# PowerBoard.net
KiCad netlist of a schematic drawn in Altium Designer
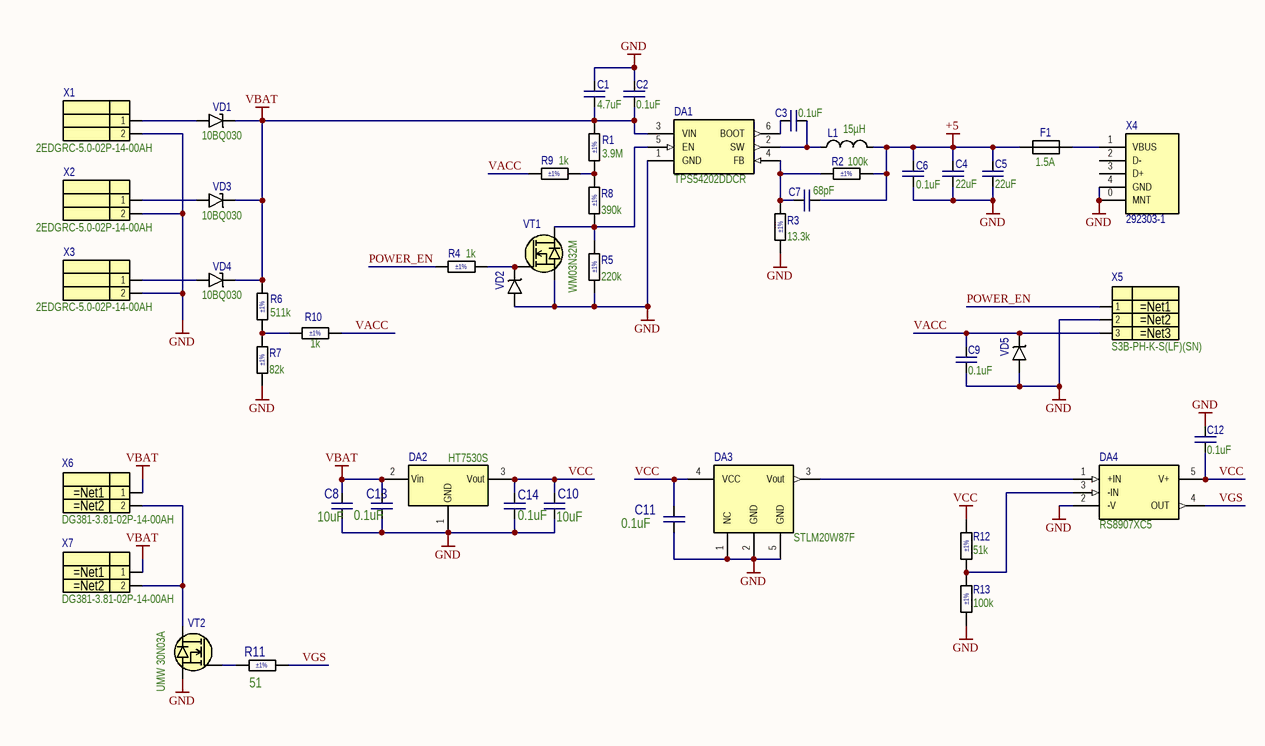
[diagram p0: PowerBoard.SchDoc]

(export (version "E")
  (design (tool "Eeschema 10.0.6"))
  (components
    (comp (ref "C1")
      (value "4.7uF")
      (footprint "C0805 (2012 Metric) N")
      (description "CAP CER 4.7UF 50V X5R 0805")
      (fields
        (field (name "PART NUMBER") "CL21A475KBQNNNE")
        (field (name "MANUFACTURER") "Samsung Electro-Mechanics")
      )
      (libsource (lib "rlc") (part "CAP"))
    )
    (comp (ref "C2")
      (value "0.1uF")
      (footprint "C0603 (1608 Metric) N")
      (description "CAP CER 0.1UF 50V X7R 0603")
      (fields
        (field (name "PART NUMBER") "CL10B104KB8NNNC")
        (field (name "MANUFACTURER") "Samsung Electro-Mechanics")
      )
      (libsource (lib "rlc") (part "CAP"))
    )
    (comp (ref "C3")
      (value "0.1uF")
      (footprint "C0603 (1608 Metric) N")
      (description "CAP CER 0.1UF 50V X7R 0603")
      (fields
        (field (name "PART NUMBER") "CL10B104KB8NNNC")
        (field (name "MANUFACTURER") "Samsung Electro-Mechanics")
      )
      (libsource (lib "rlc") (part "CAP"))
    )
    (comp (ref "C4")
      (value "22uF")
      (footprint "C0805 (2012 Metric) N")
      (description "CAP CER 22UF 10V X5R 0805")
      (fields (field (name "PART NUMBER") "CC0805MKX5R6BB226") (field (name "MANUFACTURER") "Yageo"))
      (libsource (lib "rlc") (part "CAP"))
    )
    (comp (ref "C5")
      (value "22uF")
      (footprint "C0805 (2012 Metric) N")
      (description "CAP CER 22UF 10V X5R 0805")
      (fields (field (name "PART NUMBER") "CC0805MKX5R6BB226") (field (name "MANUFACTURER") "Yageo"))
      (libsource (lib "rlc") (part "CAP"))
    )
    (comp (ref "C6")
      (value "0.1uF")
      (footprint "C0603 (1608 Metric) N")
      (description "CAP CER 0.1UF 50V X7R 0603")
      (fields
        (field (name "PART NUMBER") "CL10B104KB8NNNC")
        (field (name "MANUFACTURER") "Samsung Electro-Mechanics")
      )
      (libsource (lib "rlc") (part "CAP"))
    )
    (comp (ref "C7")
      (value "68pF")
      (footprint "C0603 (1608 Metric) N")
      (description "CAP CER 68PF 50V C0G/NPO 0603")
      (fields (field (name "PART NUMBER") "CC0603JRNPO9BN680") (field (name "MANUFACTURER") "Yageo"))
      (libsource (lib "rlc") (part "CAP"))
    )
    (comp (ref "C8")
      (value "10uF")
      (footprint "C0603 (1608 Metric) N")
      (description "CAP CER 10uF 35V C0G/NPO 0603")
      (fields (field (name "PART NUMBER") "GRM188R6YA106MA73D") (field (name "MANUFACTURER") "Yageo"))
      (libsource (lib "PowerBoard") (part "CC0603JRNPO9BN680"))
    )
    (comp (ref "C9")
      (value "0.1uF")
      (footprint "C0603 (1608 Metric) N")
      (description "CAP CER 0.1UF 50V X7R 0603")
      (fields
        (field (name "PART NUMBER") "CL10B104KB8NNNC")
        (field (name "MANUFACTURER") "Samsung Electro-Mechanics")
      )
      (libsource (lib "rlc") (part "CAP"))
    )
    (comp (ref "C10")
      (value "10uF")
      (footprint "C0603 (1608 Metric) N")
      (description "CAP CER 10uF 6.3V C0G/NPO 0603")
      (fields (field (name "PART NUMBER") "CC0603MRX6S5BB106") (field (name "MANUFACTURER") "Yageo"))
      (libsource (lib "PowerBoard") (part "CC0603JRNPO9BN680"))
    )
    (comp (ref "C11")
      (value "0.1uF")
      (footprint "C0603 (1608 Metric) N")
      (description "CAP CER 0.1uF 50V C0G/NPO 0603")
      (fields (field (name "PART NUMBER") "CC0603JRX7R9BB104") (field (name "MANUFACTURER") "Yageo"))
      (libsource (lib "PowerBoard") (part "CC0603JRNPO9BN680"))
    )
    (comp (ref "C12")
      (value "0.1uF")
      (footprint "C0603 (1608 Metric) N")
      (description "CAP CER 0.1UF 50V X7R 0603")
      (fields
        (field (name "PART NUMBER") "CL10B104KB8NNNC")
        (field (name "MANUFACTURER") "Samsung Electro-Mechanics")
      )
      (libsource (lib "rlc") (part "CAP"))
    )
    (comp (ref "C13")
      (value "0.1uF")
      (footprint "C0603 (1608 Metric) N")
      (description "CAP CER 0.1uF 50V C0G/NPO 0603")
      (fields (field (name "PART NUMBER") "CC0603JRX7R9BB104") (field (name "MANUFACTURER") "Yageo"))
      (libsource (lib "PowerBoard") (part "CC0603JRNPO9BN680"))
    )
    (comp (ref "C14")
      (value "0.1uF")
      (footprint "C0603 (1608 Metric) N")
      (description "CAP CER 0.1uF 50V C0G/NPO 0603")
      (fields (field (name "PART NUMBER") "CC0603JRX7R9BB104") (field (name "MANUFACTURER") "Yageo"))
      (libsource (lib "PowerBoard") (part "CC0603JRNPO9BN680"))
    )
    (comp (ref "DA1")
      (value "TPS54202DDCR")
      (footprint "SamacSys:SOT95P280X110-6N")
      (description "Power Supply")
      (fields (field (name "MOUSER PART NUMBER") "595-TPS54202DDCR"))
      (libsource (lib "chip_power_dcdc") (part "TPS54202"))
    )
    (comp (ref "DA2")
      (value "HT7530S")
      (footprint "SOT23-3")
      (description "Power Supply")
      (libsource (lib "PowerBoard") (part "UMW HT7530S"))
    )
    (comp (ref "DA3")
      (value "STLM20W87F")
      (footprint "STLM20DD9F - duplicate")
      (description "Ultra-low current 2.4 V precision analog temperature sensor")
      (libsource (lib "PowerBoard") (part "STLM20DD9F"))
    )
    (comp (ref "DA4")
      (value "RS8907XC5")
      (footprint "PowerBoard:SOT23-5")
      (description "Nano-Power, CMOS Input, RRIO,\r\nPush-Pull Output Comparator")
      (libsource (lib "PowerBoard") (part "RS8907XC5"))
    )
    (comp (ref "F1")
      (value "1.5A")
      (footprint "F0603 (1608 Metric) N")
      (description "PTC RESET FUSE 6V 750MA 0603")
      (fields (field (name "PART NUMBER") "0603L075SLYR") (field (name "MANUFACTURER") "Littelfuse Inc."))
      (libsource (lib "altium") (part "FusePTC"))
    )
    (comp (ref "L1")
      (value "15µH")
      (footprint "CDRH5D28")
      (description "FIXED IND 15UH 1.1A 103 MOHM SMD")
      (fields
        (field (name "PART NUMBER") "CDRH5D28NP-150NC")
        (field (name "MANUFACTURER") "Sumida America Components Inc.")
      )
      (libsource (lib "rlc") (part "IND"))
    )
    (comp (ref "R1")
      (value "3.9M")
      (footprint "R0603 (1608 Metric) N")
      (description "RES SMD 511K OHM 1% 1/10W 0603")
      (fields
        (field (name "TOLERANCE") "±1%")
        (field (name "PART NUMBER") "RC0603FR-073M9L")
        (field (name "MANUFACTURER") "Yageo")
      )
      (libsource (lib "rlc") (part "RES"))
    )
    (comp (ref "R2")
      (value "100k")
      (footprint "R0603 (1608 Metric) N")
      (description "RES SMD 100K OHM 1% 1/10W 0603")
      (fields
        (field (name "TOLERANCE") "±1%")
        (field (name "PART NUMBER") "RC0603FR-07100KL")
        (field (name "MANUFACTURER") "Yageo")
      )
      (libsource (lib "rlc") (part "RES"))
    )
    (comp (ref "R3")
      (value "13.3k")
      (footprint "R0603 (1608 Metric) N")
      (description "RES SMD 13.3K OHM 1% 1/10W 0603")
      (fields
        (field (name "TOLERANCE") "±1%")
        (field (name "PART NUMBER") "RC0603FR-0713K3L")
        (field (name "MANUFACTURER") "Yageo")
      )
      (libsource (lib "rlc") (part "RES"))
    )
    (comp (ref "R4")
      (value "1k")
      (footprint "R0603 (1608 Metric) N")
      (description "RES SMD 1K OHM 1% 1/10W 0603")
      (fields
        (field (name "TOLERANCE") "±1%")
        (field (name "PART NUMBER") "RC0603FR-071KL")
        (field (name "MANUFACTURER") "Yageo")
      )
      (libsource (lib "rlc") (part "RES"))
    )
    (comp (ref "R5")
      (value "220k")
      (footprint "R0603 (1608 Metric) N")
      (description "RES SMD 100K OHM 1% 1/10W 0603")
      (fields
        (field (name "TOLERANCE") "±1%")
        (field (name "PART NUMBER") "RC0603FR-07220KL")
        (field (name "MANUFACTURER") "Yageo")
      )
      (libsource (lib "rlc") (part "RES"))
    )
    (comp (ref "R6")
      (value "511k")
      (footprint "R0603 (1608 Metric) N")
      (description "RES SMD 511K OHM 1% 1/10W 0603")
      (fields
        (field (name "TOLERANCE") "±1%")
        (field (name "PART NUMBER") "RC0603FR-07511KL")
        (field (name "MANUFACTURER") "Yageo")
      )
      (libsource (lib "rlc") (part "RES"))
    )
    (comp (ref "R7")
      (value "82k")
      (footprint "R0603 (1608 Metric) N")
      (description "RES SMD 100K OHM 1% 1/10W 0603")
      (fields
        (field (name "TOLERANCE") "±1%")
        (field (name "PART NUMBER") "RC0603FR-0782KL")
        (field (name "MANUFACTURER") "Yageo")
      )
      (libsource (lib "rlc") (part "RES"))
    )
    (comp (ref "R8")
      (value "390k")
      (footprint "R0603 (1608 Metric) N")
      (description "RES SMD 100K OHM 1% 1/10W 0603")
      (fields
        (field (name "TOLERANCE") "±1%")
        (field (name "PART NUMBER") "RC0603FR-07390KL")
        (field (name "MANUFACTURER") "Yageo")
      )
      (libsource (lib "rlc") (part "RES"))
    )
    (comp (ref "R9")
      (value "1k")
      (footprint "R0603 (1608 Metric) N")
      (description "RES SMD 1K OHM 1% 1/10W 0603")
      (fields
        (field (name "TOLERANCE") "±1%")
        (field (name "PART NUMBER") "RC0603FR-071KL")
        (field (name "MANUFACTURER") "Yageo")
      )
      (libsource (lib "rlc") (part "RES"))
    )
    (comp (ref "R10")
      (value "1k")
      (footprint "R0603 (1608 Metric) N")
      (description "RES SMD 1K OHM 1% 1/10W 0603")
      (fields
        (field (name "TOLERANCE") "±1%")
        (field (name "PART NUMBER") "RC0603FR-071KL")
        (field (name "MANUFACTURER") "Yageo")
      )
      (libsource (lib "rlc") (part "RES"))
    )
    (comp (ref "R11")
      (value "51")
      (footprint "R0603 (1608 Metric) N")
      (description "RES SMD 51 OHM 1% 1/10W 0603")
      (fields
        (field (name "TOLERANCE") "±1%")
        (field (name "PART NUMBER") "RC0603FR-0751RL")
        (field (name "MANUFACTURER") "Yageo")
      )
      (libsource (lib "rlc") (part "RES"))
    )
    (comp (ref "R12")
      (value "51k")
      (footprint "R0603 (1608 Metric) N")
      (description "RES SMD 1K OHM 1% 1/10W 0603")
      (fields
        (field (name "TOLERANCE") "±1%")
        (field (name "PART NUMBER") "RC0603FR-0751KL")
        (field (name "MANUFACTURER") "Yageo")
      )
      (libsource (lib "rlc") (part "RES"))
    )
    (comp (ref "R13")
      (value "100k")
      (footprint "R0603 (1608 Metric) N")
      (description "RES SMD 100K OHM 1% 1/10W 0603")
      (fields
        (field (name "TOLERANCE") "±1%")
        (field (name "PART NUMBER") "RC0603FR-07100KL")
        (field (name "MANUFACTURER") "Yageo")
      )
      (libsource (lib "rlc") (part "RES"))
    )
    (comp (ref "VD1")
      (value "10BQ030")
      (footprint "DO-214AA ( SMB )")
      (description "DIODE SCHOTTKY 30V 1A SMB")
      (fields (field (name "MANUFACTURER") "Vishay Semiconductor Diodes Division"))
      (libsource (lib "diode") (part "DiodeSchottky"))
    )
    (comp (ref "VD2")
      (value "PESD12VS1UB")
      (footprint "SOD-523")
      (description "ESD protection diodes")
      (fields (field (name "MANUFACTURER") "Nexperia"))
      (libsource (lib "diode") (part "DiodeTVS"))
    )
    (comp (ref "VD3")
      (value "10BQ030")
      (footprint "DO-214AA ( SMB )")
      (description "DIODE SCHOTTKY 30V 1A SMB")
      (fields (field (name "MANUFACTURER") "Vishay Semiconductor Diodes Division"))
      (libsource (lib "diode") (part "DiodeSchottky"))
    )
    (comp (ref "VD4")
      (value "10BQ030")
      (footprint "DO-214AA ( SMB )")
      (description "DIODE SCHOTTKY 30V 1A SMB")
      (fields (field (name "MANUFACTURER") "Vishay Semiconductor Diodes Division"))
      (libsource (lib "diode") (part "DiodeSchottky"))
    )
    (comp (ref "VD5")
      (value "PESD12VS1UB")
      (footprint "SOD-523")
      (description "ESD protection diodes")
      (fields (field (name "MANUFACTURER") "Nexperia"))
      (libsource (lib "diode") (part "DiodeTVS"))
    )
    (comp (ref "VT1")
      (value "WM03N32M")
      (footprint "SOT95P245X110-3N")
      (description "N-Channel MOSFET")
      (fields (field (name "MANUFACTURER") "way-on"))
      (libsource (lib "transistor") (part "MOSFET_N"))
    )
    (comp (ref "VT2")
      (value "UMW 30N03A")
      (footprint "TO-252")
      (description "30V N-Channel Power")
      (libsource (lib "PowerBoard") (part "UMW 30N03A"))
    )
    (comp (ref "X1")
      (value "2EDGRC-5.0-02P-14-00AH")
      (footprint "2EDGRC-5.0-02P-14")
      (description "TERM BLOCK HDR 2POS 90DEG 5MM")
      (fields (field (name "MANUFACTURER") "Degson"))
      (libsource (lib "terminals") (part "Terminal_2_pin"))
    )
    (comp (ref "X2")
      (value "2EDGRC-5.0-02P-14-00AH")
      (footprint "2EDGRC-5.0-02P-14")
      (description "TERM BLOCK HDR 2POS 90DEG 5MM")
      (fields (field (name "MANUFACTURER") "Degson"))
      (libsource (lib "terminals") (part "Terminal_2_pin"))
    )
    (comp (ref "X3")
      (value "2EDGRC-5.0-02P-14-00AH")
      (footprint "2EDGRC-5.0-02P-14")
      (description "TERM BLOCK HDR 2POS 90DEG 5MM")
      (fields (field (name "MANUFACTURER") "Degson"))
      (libsource (lib "terminals") (part "Terminal_2_pin"))
    )
    (comp (ref "X4")
      (value "292303-1")
      (footprint "TE-292303-1")
      (description "USB A R/A RCPT ASSY SMT")
      (libsource (lib "PowerBoard") (part "292303-1"))
    )
    (comp (ref "X5")
      (value "S3B-PH-K-S(LF)(SN)")
      (footprint "S3B-PH-K-S(LF)(SN)")
      (description "CONN HEADER SMD R/A 3POS 2MM")
      (libsource (lib "PowerBoard") (part "S3B-PH-K-S(LF)(SN)"))
    )
    (comp (ref "X6")
      (value "DG381-3.81-02P-14-00AH")
      (footprint "DG381-3.81-02P-14-00AH")
      (libsource (lib "PowerBoard") (part "DG381-3.81-02P-14-00AH"))
    )
    (comp (ref "X7")
      (value "DG381-3.81-02P-14-00AH")
      (footprint "PowerBoard:DG381-3.81-02P-14-00AH")
      (libsource (lib "PowerBoard") (part "DG381-3.81-02P-14-00AH"))
    )
  )
  (nets
    (net (code "1") (name "+5") (class "Default")
      (node (ref "C4") (pin "1") (pinfunction "1_1") (pintype "passive"))
      (node (ref "C5") (pin "1") (pinfunction "1_1") (pintype "passive"))
      (node (ref "C6") (pin "2") (pinfunction "2_2") (pintype "passive"))
      (node (ref "C7") (pin "2") (pinfunction "2_2") (pintype "passive"))
      (node (ref "F1") (pin "1") (pintype "passive"))
      (node (ref "L1") (pin "2") (pinfunction "2_2") (pintype "passive"))
      (node (ref "R2") (pin "2") (pinfunction "2_2") (pintype "passive"))
    )
    (net (code "2") (name "/POWER_EN") (class "Default")
      (node (ref "R4") (pin "1") (pinfunction "1_1") (pintype "passive"))
      (node (ref "X5") (pin "1") (pinfunction "1_1") (pintype "passive"))
    )
    (net (code "3") (name "/VACC") (class "Default")
      (node (ref "C9") (pin "2") (pinfunction "2_2") (pintype "passive"))
      (node (ref "R10") (pin "2") (pinfunction "2_2") (pintype "passive"))
      (node (ref "R9") (pin "1") (pinfunction "1_1") (pintype "passive"))
      (node (ref "VD5") (pin "C") (pinfunction "C_C") (pintype "passive"))
      (node (ref "X5") (pin "3") (pinfunction "3_3") (pintype "passive"))
    )
    (net (code "4") (name "/VGS") (class "Default")
      (node (ref "DA4") (pin "4") (pinfunction "OUT_4") (pintype "output"))
      (node (ref "R11") (pin "2") (pinfunction "2_2") (pintype "passive"))
    )
    (net (code "5") (name "GND") (class "Default")
      (node (ref "C1") (pin "1") (pinfunction "1_1") (pintype "passive"))
      (node (ref "C10") (pin "2") (pinfunction "2_2") (pintype "passive"))
      (node (ref "C11") (pin "2") (pinfunction "2_2") (pintype "passive"))
      (node (ref "C12") (pin "2") (pinfunction "2_2") (pintype "passive"))
      (node (ref "C13") (pin "2") (pinfunction "2_2") (pintype "passive"))
      (node (ref "C14") (pin "2") (pinfunction "2_2") (pintype "passive"))
      (node (ref "C2") (pin "2") (pinfunction "2_2") (pintype "passive"))
      (node (ref "C4") (pin "2") (pinfunction "2_2") (pintype "passive"))
      (node (ref "C5") (pin "2") (pinfunction "2_2") (pintype "passive"))
      (node (ref "C6") (pin "1") (pinfunction "1_1") (pintype "passive"))
      (node (ref "C8") (pin "2") (pinfunction "2_2") (pintype "passive"))
      (node (ref "C9") (pin "1") (pinfunction "1_1") (pintype "passive"))
      (node (ref "DA1") (pin "1") (pinfunction "GND_1") (pintype "power_in"))
      (node (ref "DA2") (pin "1") (pinfunction "GND_1") (pintype "power_in"))
      (node (ref "DA3") (pin "1") (pinfunction "NC_1") (pintype "power_in"))
      (node (ref "DA3") (pin "2") (pinfunction "GND_2") (pintype "power_in"))
      (node (ref "DA3") (pin "5") (pinfunction "GND_5") (pintype "power_in"))
      (node (ref "DA4") (pin "2") (pinfunction "-V_2") (pintype "power_in"))
      (node (ref "R13") (pin "1") (pinfunction "1_1") (pintype "passive"))
      (node (ref "R3") (pin "1") (pinfunction "1_1") (pintype "passive"))
      (node (ref "R5") (pin "1") (pinfunction "1_1") (pintype "passive"))
      (node (ref "R7") (pin "1") (pinfunction "1_1") (pintype "passive"))
      (node (ref "VD2") (pin "A") (pinfunction "A_A") (pintype "passive"))
      (node (ref "VD5") (pin "A") (pinfunction "A_A") (pintype "passive"))
      (node (ref "VT1") (pin "S") (pinfunction "S_S") (pintype "passive"))
      (node (ref "VT2") (pin "S") (pinfunction "S_S") (pintype "passive"))
      (node (ref "X1") (pin "2") (pinfunction "2_2") (pintype "passive"))
      (node (ref "X2") (pin "2") (pinfunction "2_2") (pintype "passive"))
      (node (ref "X3") (pin "2") (pinfunction "2_2") (pintype "passive"))
      (node (ref "X4") (pin "0") (pinfunction "MNT_0") (pintype "passive"))
      (node (ref "X4") (pin "4") (pinfunction "GND_4") (pintype "passive"))
      (node (ref "X5") (pin "2") (pinfunction "2_2") (pintype "passive"))
    )
    (net (code "6") (name "Net-(DA1-BOOT)") (class "Default")
      (node (ref "C3") (pin "1") (pinfunction "1_1") (pintype "passive"))
      (node (ref "DA1") (pin "6") (pinfunction "BOOT_6") (pintype "output"))
    )
    (net (code "7") (name "Net-(DA1-EN)") (class "Default")
      (node (ref "DA1") (pin "5") (pinfunction "EN_5") (pintype "input"))
      (node (ref "R5") (pin "2") (pinfunction "2_2") (pintype "passive"))
      (node (ref "R8") (pin "1") (pinfunction "1_1") (pintype "passive"))
      (node (ref "VT1") (pin "D") (pinfunction "D_D") (pintype "passive"))
    )
    (net (code "8") (name "Net-(DA1-FB)") (class "Default")
      (node (ref "C7") (pin "1") (pinfunction "1_1") (pintype "passive"))
      (node (ref "DA1") (pin "4") (pinfunction "FB_4") (pintype "input"))
      (node (ref "R2") (pin "1") (pinfunction "1_1") (pintype "passive"))
      (node (ref "R3") (pin "2") (pinfunction "2_2") (pintype "passive"))
    )
    (net (code "9") (name "Net-(DA1-SW)") (class "Default")
      (node (ref "C3") (pin "2") (pinfunction "2_2") (pintype "passive"))
      (node (ref "DA1") (pin "2") (pinfunction "SW_2") (pintype "output"))
      (node (ref "L1") (pin "1") (pinfunction "1_1") (pintype "passive"))
    )
    (net (code "10") (name "Net-(DA3-Vout)") (class "Default")
      (node (ref "DA3") (pin "3") (pinfunction "Vout_3") (pintype "output"))
      (node (ref "DA4") (pin "1") (pinfunction "+IN_1") (pintype "input"))
    )
    (net (code "11") (name "Net-(DA4--IN)") (class "Default")
      (node (ref "DA4") (pin "3") (pinfunction "-IN_3") (pintype "input"))
      (node (ref "R12") (pin "1") (pinfunction "1_1") (pintype "passive"))
      (node (ref "R13") (pin "2") (pinfunction "2_2") (pintype "passive"))
    )
    (net (code "12") (name "Net-(R1-Pad1)") (class "Default")
      (node (ref "R1") (pin "1") (pinfunction "1_1") (pintype "passive"))
      (node (ref "R8") (pin "2") (pinfunction "2_2") (pintype "passive"))
      (node (ref "R9") (pin "2") (pinfunction "2_2") (pintype "passive"))
    )
    (net (code "13") (name "Net-(R4-Pad2)") (class "Default")
      (node (ref "R4") (pin "2") (pinfunction "2_2") (pintype "passive"))
      (node (ref "VD2") (pin "C") (pinfunction "C_C") (pintype "passive"))
      (node (ref "VT1") (pin "G") (pinfunction "G_G") (pintype "passive"))
    )
    (net (code "14") (name "Net-(R10-Pad1)") (class "Default")
      (node (ref "R10") (pin "1") (pinfunction "1_1") (pintype "passive"))
      (node (ref "R6") (pin "1") (pinfunction "1_1") (pintype "passive"))
      (node (ref "R7") (pin "2") (pinfunction "2_2") (pintype "passive"))
    )
    (net (code "15") (name "Net-(R11-Pad1)") (class "Default")
      (node (ref "R11") (pin "1") (pinfunction "1_1") (pintype "passive"))
      (node (ref "VT2") (pin "G") (pinfunction "G_G") (pintype "passive"))
    )
    (net (code "16") (name "Net-(VD1-PadA)") (class "Default")
      (node (ref "VD1") (pin "A") (pinfunction "A_A") (pintype "passive"))
      (node (ref "X1") (pin "1") (pinfunction "1_1") (pintype "passive"))
    )
    (net (code "17") (name "Net-(VD3-PadA)") (class "Default")
      (node (ref "VD3") (pin "A") (pinfunction "A_A") (pintype "passive"))
      (node (ref "X2") (pin "1") (pinfunction "1_1") (pintype "passive"))
    )
    (net (code "18") (name "Net-(VD4-PadA)") (class "Default")
      (node (ref "VD4") (pin "A") (pinfunction "A_A") (pintype "passive"))
      (node (ref "X3") (pin "1") (pinfunction "1_1") (pintype "passive"))
    )
    (net (code "19") (name "Net-(VT2-PadD)") (class "Default")
      (node (ref "VT2") (pin "D") (pinfunction "D_D") (pintype "passive"))
      (node (ref "X6") (pin "2") (pinfunction "2_2") (pintype "passive"))
      (node (ref "X7") (pin "2") (pinfunction "2_2") (pintype "passive"))
    )
    (net (code "20") (name "Net-(X4-VBUS)") (class "Default")
      (node (ref "F1") (pin "2") (pintype "passive"))
      (node (ref "X4") (pin "1") (pinfunction "VBUS_1") (pintype "passive"))
    )
    (net (code "21") (name "VBAT") (class "Default")
      (node (ref "C1") (pin "2") (pinfunction "2_2") (pintype "passive"))
      (node (ref "C13") (pin "1") (pinfunction "1_1") (pintype "passive"))
      (node (ref "C2") (pin "1") (pinfunction "1_1") (pintype "passive"))
      (node (ref "C8") (pin "1") (pinfunction "1_1") (pintype "passive"))
      (node (ref "DA1") (pin "3") (pinfunction "VIN_3") (pintype "power_in"))
      (node (ref "DA2") (pin "2") (pinfunction "Vin_2") (pintype "power_in"))
      (node (ref "R1") (pin "2") (pinfunction "2_2") (pintype "passive"))
      (node (ref "R6") (pin "2") (pinfunction "2_2") (pintype "passive"))
      (node (ref "VD1") (pin "C") (pinfunction "C_C") (pintype "passive"))
      (node (ref "VD3") (pin "C") (pinfunction "C_C") (pintype "passive"))
      (node (ref "VD4") (pin "C") (pinfunction "C_C") (pintype "passive"))
      (node (ref "X6") (pin "1") (pinfunction "1_1") (pintype "passive"))
      (node (ref "X7") (pin "1") (pinfunction "1_1") (pintype "passive"))
    )
    (net (code "22") (name "VCC") (class "Default")
      (node (ref "C10") (pin "1") (pinfunction "1_1") (pintype "passive"))
      (node (ref "C11") (pin "1") (pinfunction "1_1") (pintype "passive"))
      (node (ref "C12") (pin "1") (pinfunction "1_1") (pintype "passive"))
      (node (ref "C14") (pin "1") (pinfunction "1_1") (pintype "passive"))
      (node (ref "DA2") (pin "3") (pinfunction "Vout_3") (pintype "power_in"))
      (node (ref "DA3") (pin "4") (pinfunction "VCC_4") (pintype "power_in"))
      (node (ref "DA4") (pin "5") (pinfunction "V+_5") (pintype "power_in"))
      (node (ref "R12") (pin "2") (pinfunction "2_2") (pintype "passive"))
    )
    (net (code "23") (name "unconnected-(X4-D+-Pad3)") (class "Default")
      (node (ref "X4") (pin "3") (pinfunction "D+_3") (pintype "passive"))
    )
    (net (code "24") (name "unconnected-(X4-D--Pad2)") (class "Default")
      (node (ref "X4") (pin "2") (pinfunction "D-_2") (pintype "passive"))
    )
  )
)
